# MCU.net
KiCad netlist of a schematic drawn in Altium Designer
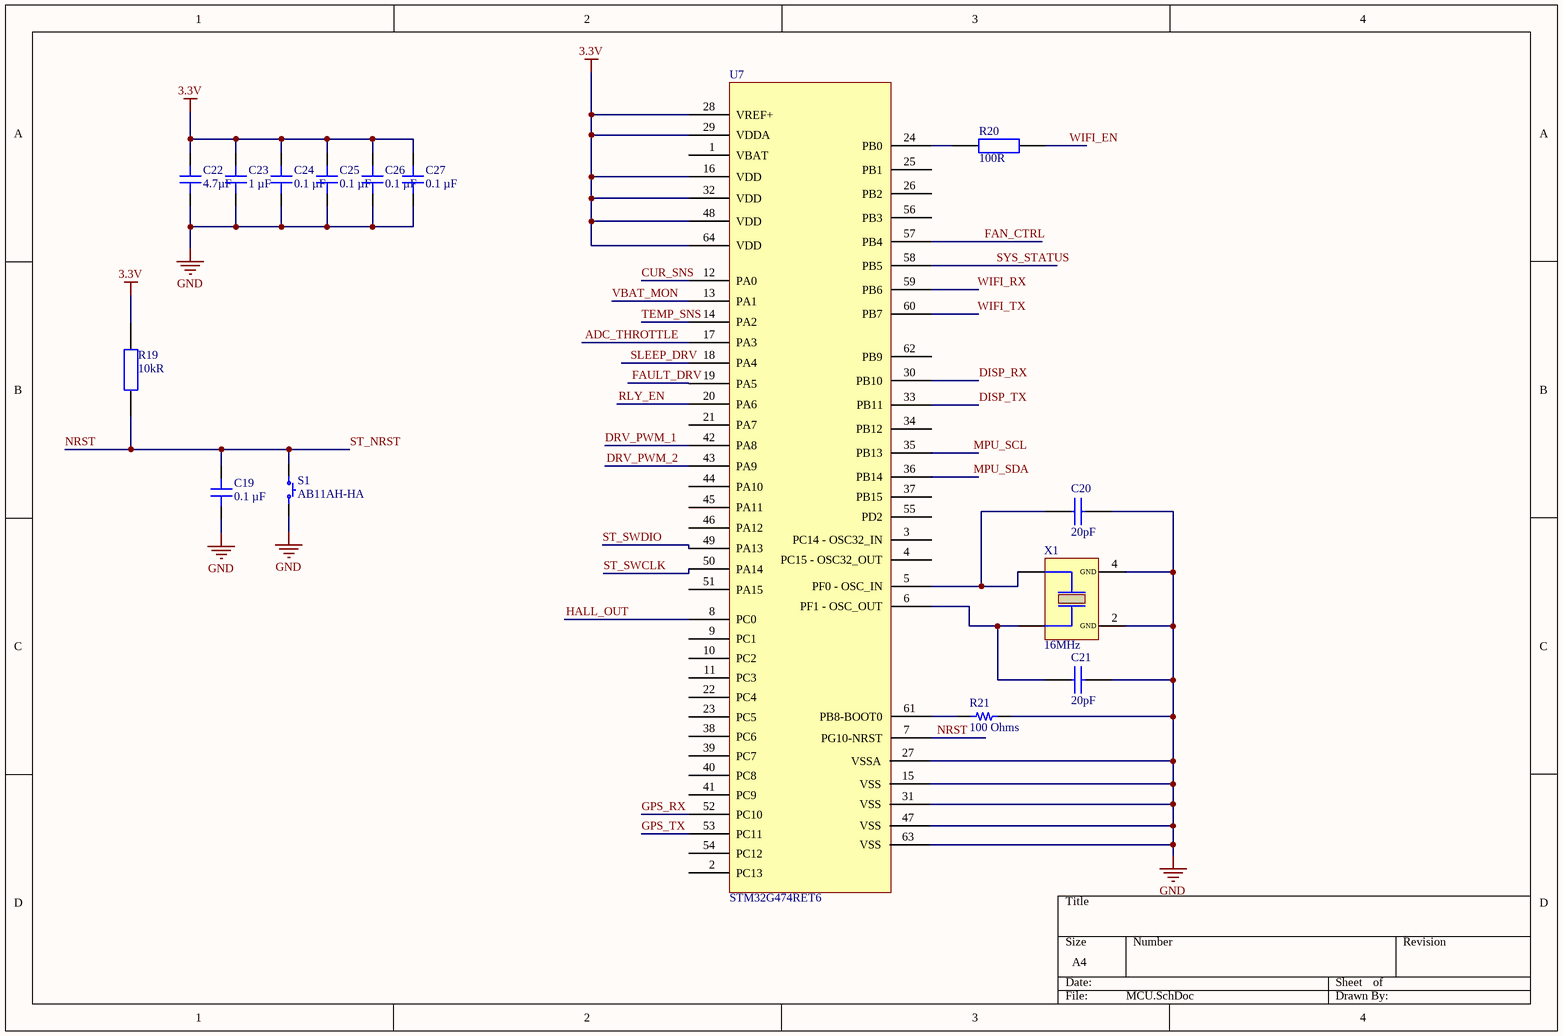
[diagram p0: MCU.SchDoc]

(export (version "E")
  (design (tool "Eeschema 10.0.6"))
  (components
    (comp (ref "C19")
      (value "0.1 µF")
      (footprint "CAP 0603_1608")
      (description "CAP CER 0.1UF 16V X7R 0603")
      (fields
        (field (name "PART NUMBER") "CS0603KRX7R7BB104")
        (field (name "CAPACITANCE") "0.1 µF")
        (field (name "MANUFACTURER") "Yageo")
      )
      (libsource (lib "Celestial Altium Library - altium_library") (part "Capacitor"))
    )
    (comp (ref "C20")
      (value "CL10C200JB8NNNC")
      (footprint "CAP_0603")
      (description "CAP CER 20pF %5 0603 SMD")
      (fields
        (field (name "MANUFACTURER") "Samsung")
        (field (name "TOLERANCE") "5%")
        (field (name "CAPACITANCE") "20pF")
        (field (name "DESIGNED BY") "BERK")
      )
      (libsource (lib "UDEMY_Library") (part "CAP CER 20pF 0603"))
    )
    (comp (ref "C21")
      (value "CL10C200JB8NNNC")
      (footprint "CAP_0603")
      (description "CAP CER 20pF %5 0603 SMD")
      (fields
        (field (name "MANUFACTURER") "Samsung")
        (field (name "TOLERANCE") "5%")
        (field (name "CAPACITANCE") "20pF")
        (field (name "DESIGNED BY") "BERK")
      )
      (libsource (lib "UDEMY_Library") (part "CAP CER 20pF 0603"))
    )
    (comp (ref "C22")
      (value "4.7µF")
      (footprint "CAP 0805_2012")
      (description "CAP CER 4.7UF 16V X5R 0805")
      (fields
        (field (name "PART NUMBER") "0805YD475MAT2A")
        (field (name "CAPACITANCE") "4.7µF")
        (field (name "MANUFACTURER") "AVX Corporation")
      )
      (libsource (lib "Celestial Altium Library - altium_library") (part "Capacitor"))
    )
    (comp (ref "C23")
      (value "1 µF")
      (footprint "CAP 0805_2012")
      (description "CAP CER 1UF 16V X7R 0805")
      (fields
        (field (name "PART NUMBER") "EMK212B7105KGHTR")
        (field (name "CAPACITANCE") "1 µF")
        (field (name "MANUFACTURER") "Taiyo Yuden")
      )
      (libsource (lib "Celestial Altium Library - altium_library") (part "Capacitor"))
    )
    (comp (ref "C24")
      (value "0.1 µF")
      (footprint "CAP 0603_1608")
      (description "CAP CER 0.1UF 16V X7R 0603")
      (fields
        (field (name "PART NUMBER") "CS0603KRX7R7BB104")
        (field (name "CAPACITANCE") "0.1 µF")
        (field (name "MANUFACTURER") "Yageo")
      )
      (libsource (lib "Celestial Altium Library - altium_library") (part "Capacitor"))
    )
    (comp (ref "C25")
      (value "0.1 µF")
      (footprint "CAP 0603_1608")
      (description "CAP CER 0.1UF 16V X7R 0603")
      (fields
        (field (name "PART NUMBER") "CS0603KRX7R7BB104")
        (field (name "CAPACITANCE") "0.1 µF")
        (field (name "MANUFACTURER") "Yageo")
      )
      (libsource (lib "Celestial Altium Library - altium_library") (part "Capacitor"))
    )
    (comp (ref "C26")
      (value "0.1 µF")
      (footprint "CAP 0603_1608")
      (description "CAP CER 0.1UF 16V X7R 0603")
      (fields
        (field (name "PART NUMBER") "CS0603KRX7R7BB104")
        (field (name "CAPACITANCE") "0.1 µF")
        (field (name "MANUFACTURER") "Yageo")
      )
      (libsource (lib "Celestial Altium Library - altium_library") (part "Capacitor"))
    )
    (comp (ref "C27")
      (value "0.1 µF")
      (footprint "CAP 0603_1608")
      (description "CAP CER 0.1UF 16V X7R 0603")
      (fields
        (field (name "PART NUMBER") "CS0603KRX7R7BB104")
        (field (name "CAPACITANCE") "0.1 µF")
        (field (name "MANUFACTURER") "Yageo")
      )
      (libsource (lib "Celestial Altium Library - altium_library") (part "Capacitor"))
    )
    (comp (ref "R19")
      (value "RC0603FR-0710KL")
      (footprint "RES_0603")
      (description "RES 10K %1 OHM 0603 SMD")
      (fields
        (field (name "MANUFACTURER") "Yageo")
        (field (name "TOLERANCE") "1%")
        (field (name "RESISTANCE") "10kR")
        (field (name "DESIGNED BY") "BERK")
      )
      (libsource (lib "UDEMY_Library") (part "RES 10K OHM 0603"))
    )
    (comp (ref "R20")
      (value "RC0603JR-07100RL")
      (footprint "RES_0603")
      (description "RES 100 %5 OHM 0603 SMD")
      (fields
        (field (name "MANUFACTURER") "Yageo")
        (field (name "TOLERANCE") "5%")
        (field (name "RESISTANCE") "100R")
        (field (name "DESIGNED BY") "BERK")
      )
      (libsource (lib "UDEMY_Library") (part "RES 100 OHM 0603"))
    )
    (comp (ref "R21")
      (value "100 Ohms")
      (footprint "RES 0603_1608")
      (description "RES SMD 100 OHM 5% 1/4W 0603")
      (fields (field (name "PART NUMBER") "ESR03EZPJ101") (field (name "MANUFACTURER") "Rohm Semiconductor"))
      (libsource (lib "Celestial Altium Library - altium_library") (part "Resistor"))
    )
    (comp (ref "S1")
      (value "AB11AH-HA")
      (footprint "NKK AB11AH-HA")
      (description "SWITCH PUSH SPST-NO 0.4VA 28V")
      (fields (field (name "MANUFACTURER") "NKK Switches"))
      (libsource (lib "Celestial Altium Library - altium_library") (part "NKK AB11AH-HA"))
    )
    (comp (ref "U7")
      (value "STM32G474RET6")
      (footprint "STM32G474RET6")
      (description "MCU 32-bit ARM Cortex M4 RISC 512KB Flash 1.8V/2.5V/3.3V 64-Pin LQFP Tray")
      (fields (field (name "MANUFACTURER") "STMicroelectronics"))
      (libsource (lib "TIDA_00620") (part "STM32G474RET6"))
    )
    (comp (ref "X1")
      (value "ECS-160-20-30B-TR")
      (footprint "ECS")
      (description "CRYSTAL 16.0000MHZ 20PF SMD")
      (fields
        (field (name "MANUFACTURER") "ECS International")
        (field (name "TOLERANCE") "50ppm")
        (field (name "FREQUENCY") "16MHz")
        (field (name "DESIGNED BY") "BERK")
      )
      (libsource (lib "UDEMY_Library") (part "CRYSTAL 16MHz"))
    )
  )
  (nets
    (net (code "1") (name "/ADC_THROTTLE") (class "Default")
      (node (ref "U7") (pin "17") (pinfunction "PA3_17") (pintype "passive"))
    )
    (net (code "2") (name "/CUR_SNS") (class "Default")
      (node (ref "U7") (pin "12") (pinfunction "PA0_12") (pintype "passive"))
    )
    (net (code "3") (name "/DISP_RX") (class "Default")
      (node (ref "U7") (pin "30") (pinfunction "PB10_30") (pintype "passive"))
    )
    (net (code "4") (name "/DISP_TX") (class "Default")
      (node (ref "U7") (pin "33") (pinfunction "PB11_33") (pintype "passive"))
    )
    (net (code "5") (name "/DRV_PWM_1") (class "Default")
      (node (ref "U7") (pin "42") (pinfunction "PA8_42") (pintype "passive"))
    )
    (net (code "6") (name "/DRV_PWM_2") (class "Default")
      (node (ref "U7") (pin "43") (pinfunction "PA9_43") (pintype "passive"))
    )
    (net (code "7") (name "/FAN_CTRL") (class "Default")
      (node (ref "U7") (pin "57") (pinfunction "PB4_57") (pintype "passive"))
    )
    (net (code "8") (name "/FAULT_DRV") (class "Default")
      (node (ref "U7") (pin "19") (pinfunction "PA5_19") (pintype "passive"))
    )
    (net (code "9") (name "/GPS_RX") (class "Default")
      (node (ref "U7") (pin "52") (pinfunction "PC10_52") (pintype "passive"))
    )
    (net (code "10") (name "/GPS_TX") (class "Default")
      (node (ref "U7") (pin "53") (pinfunction "PC11_53") (pintype "passive"))
    )
    (net (code "11") (name "/HALL_OUT") (class "Default")
      (node (ref "U7") (pin "8") (pinfunction "PC0_8") (pintype "passive"))
    )
    (net (code "12") (name "/MPU_SCL") (class "Default")
      (node (ref "U7") (pin "35") (pinfunction "PB13_35") (pintype "passive"))
    )
    (net (code "13") (name "/MPU_SDA") (class "Default")
      (node (ref "U7") (pin "36") (pinfunction "PB14_36") (pintype "passive"))
    )
    (net (code "14") (name "/NRST") (class "Default")
      (node (ref "C19") (pin "2") (pinfunction "2_2") (pintype "passive"))
      (node (ref "R19") (pin "1") (pinfunction "1_1") (pintype "passive"))
      (node (ref "S1") (pin "1") (pinfunction "1_1") (pintype "passive"))
      (node (ref "U7") (pin "7") (pinfunction "PG10-NRST_7") (pintype "passive"))
    )
    (net (code "15") (name "/RLY_EN") (class "Default")
      (node (ref "U7") (pin "20") (pinfunction "PA6_20") (pintype "passive"))
    )
    (net (code "16") (name "/SLEEP_DRV") (class "Default")
      (node (ref "U7") (pin "18") (pinfunction "PA4_18") (pintype "passive"))
    )
    (net (code "17") (name "/ST_SWCLK") (class "Default")
      (node (ref "U7") (pin "50") (pinfunction "PA14_50") (pintype "passive"))
    )
    (net (code "18") (name "/ST_SWDIO") (class "Default")
      (node (ref "U7") (pin "49") (pinfunction "PA13_49") (pintype "passive"))
    )
    (net (code "19") (name "/SYS_STATUS") (class "Default")
      (node (ref "U7") (pin "58") (pinfunction "PB5_58") (pintype "passive"))
    )
    (net (code "20") (name "/TEMP_SNS") (class "Default")
      (node (ref "U7") (pin "14") (pinfunction "PA2_14") (pintype "passive"))
    )
    (net (code "21") (name "/VBAT_MON") (class "Default")
      (node (ref "U7") (pin "13") (pinfunction "PA1_13") (pintype "passive"))
    )
    (net (code "22") (name "/WIFI_EN") (class "Default")
      (node (ref "R20") (pin "2") (pinfunction "2_2") (pintype "passive"))
    )
    (net (code "23") (name "/WIFI_RX") (class "Default")
      (node (ref "U7") (pin "59") (pinfunction "PB6_59") (pintype "passive"))
    )
    (net (code "24") (name "/WIFI_TX") (class "Default")
      (node (ref "U7") (pin "60") (pinfunction "PB7_60") (pintype "passive"))
    )
    (net (code "25") (name "3.3V") (class "Default")
      (node (ref "C22") (pin "2") (pinfunction "2_2") (pintype "passive"))
      (node (ref "C23") (pin "2") (pinfunction "2_2") (pintype "passive"))
      (node (ref "C24") (pin "2") (pinfunction "2_2") (pintype "passive"))
      (node (ref "C25") (pin "2") (pinfunction "2_2") (pintype "passive"))
      (node (ref "C26") (pin "2") (pinfunction "2_2") (pintype "passive"))
      (node (ref "C27") (pin "2") (pinfunction "2_2") (pintype "passive"))
      (node (ref "R19") (pin "2") (pinfunction "2_2") (pintype "passive"))
      (node (ref "U7") (pin "16") (pinfunction "VDD_16") (pintype "passive"))
      (node (ref "U7") (pin "28") (pinfunction "VREF+_28") (pintype "passive"))
      (node (ref "U7") (pin "29") (pinfunction "VDDA_29") (pintype "passive"))
      (node (ref "U7") (pin "32") (pinfunction "VDD_32") (pintype "passive"))
      (node (ref "U7") (pin "48") (pinfunction "VDD_48") (pintype "passive"))
      (node (ref "U7") (pin "64") (pinfunction "VDD_64") (pintype "passive"))
    )
    (net (code "26") (name "GND") (class "Default")
      (node (ref "C19") (pin "1") (pinfunction "1_1") (pintype "passive"))
      (node (ref "C20") (pin "2") (pinfunction "2_2") (pintype "passive"))
      (node (ref "C21") (pin "2") (pinfunction "2_2") (pintype "passive"))
      (node (ref "C22") (pin "1") (pinfunction "1_1") (pintype "passive"))
      (node (ref "C23") (pin "1") (pinfunction "1_1") (pintype "passive"))
      (node (ref "C24") (pin "1") (pinfunction "1_1") (pintype "passive"))
      (node (ref "C25") (pin "1") (pinfunction "1_1") (pintype "passive"))
      (node (ref "C26") (pin "1") (pinfunction "1_1") (pintype "passive"))
      (node (ref "C27") (pin "1") (pinfunction "1_1") (pintype "passive"))
      (node (ref "R21") (pin "2") (pinfunction "2_2") (pintype "passive"))
      (node (ref "S1") (pin "3") (pinfunction "3_3") (pintype "passive"))
      (node (ref "U7") (pin "15") (pinfunction "VSS_15") (pintype "passive"))
      (node (ref "U7") (pin "27") (pinfunction "VSSA_27") (pintype "passive"))
      (node (ref "U7") (pin "31") (pinfunction "VSS_31") (pintype "passive"))
      (node (ref "U7") (pin "47") (pinfunction "VSS_47") (pintype "passive"))
      (node (ref "U7") (pin "63") (pinfunction "VSS_63") (pintype "passive"))
      (node (ref "X1") (pin "2") (pinfunction "GND_2") (pintype "passive"))
      (node (ref "X1") (pin "4") (pinfunction "GND_4") (pintype "passive"))
    )
    (net (code "27") (name "Net-(U7-PB0)") (class "Default")
      (node (ref "R20") (pin "1") (pinfunction "1_1") (pintype "passive"))
      (node (ref "U7") (pin "24") (pinfunction "PB0_24") (pintype "passive"))
    )
    (net (code "28") (name "Net-(U7-PB8-BOOT0)") (class "Default")
      (node (ref "R21") (pin "1") (pinfunction "1_1") (pintype "passive"))
      (node (ref "U7") (pin "61") (pinfunction "PB8-BOOT0_61") (pintype "passive"))
    )
    (net (code "29") (name "Net-(U7-PF0_-_OSC_IN)") (class "Default")
      (node (ref "C20") (pin "1") (pinfunction "1_1") (pintype "passive"))
      (node (ref "U7") (pin "5") (pinfunction "PF0_-_OSC_IN_5") (pintype "passive"))
      (node (ref "X1") (pin "3") (pinfunction "3_3") (pintype "passive"))
    )
    (net (code "30") (name "Net-(U7-PF1_-_OSC_OUT)") (class "Default")
      (node (ref "C21") (pin "1") (pinfunction "1_1") (pintype "passive"))
      (node (ref "U7") (pin "6") (pinfunction "PF1_-_OSC_OUT_6") (pintype "passive"))
      (node (ref "X1") (pin "1") (pinfunction "1_1") (pintype "passive"))
    )
    (net (code "31") (name "unconnected-(U7-PA7-Pad21)") (class "Default")
      (node (ref "U7") (pin "21") (pinfunction "PA7_21") (pintype "passive"))
    )
    (net (code "32") (name "unconnected-(U7-PA10-Pad44)") (class "Default")
      (node (ref "U7") (pin "44") (pinfunction "PA10_44") (pintype "passive"))
    )
    (net (code "33") (name "unconnected-(U7-PA11-Pad45)") (class "Default")
      (node (ref "U7") (pin "45") (pinfunction "PA11_45") (pintype "passive"))
    )
    (net (code "34") (name "unconnected-(U7-PA12-Pad46)") (class "Default")
      (node (ref "U7") (pin "46") (pinfunction "PA12_46") (pintype "passive"))
    )
    (net (code "35") (name "unconnected-(U7-PA15-Pad51)") (class "Default")
      (node (ref "U7") (pin "51") (pinfunction "PA15_51") (pintype "passive"))
    )
    (net (code "36") (name "unconnected-(U7-PB1-Pad25)") (class "Default")
      (node (ref "U7") (pin "25") (pinfunction "PB1_25") (pintype "passive"))
    )
    (net (code "37") (name "unconnected-(U7-PB2-Pad26)") (class "Default")
      (node (ref "U7") (pin "26") (pinfunction "PB2_26") (pintype "passive"))
    )
    (net (code "38") (name "unconnected-(U7-PB3-Pad56)") (class "Default")
      (node (ref "U7") (pin "56") (pinfunction "PB3_56") (pintype "passive"))
    )
    (net (code "39") (name "unconnected-(U7-PB9-Pad62)") (class "Default")
      (node (ref "U7") (pin "62") (pinfunction "PB9_62") (pintype "passive"))
    )
    (net (code "40") (name "unconnected-(U7-PB12-Pad34)") (class "Default")
      (node (ref "U7") (pin "34") (pinfunction "PB12_34") (pintype "passive"))
    )
    (net (code "41") (name "unconnected-(U7-PB15-Pad37)") (class "Default")
      (node (ref "U7") (pin "37") (pinfunction "PB15_37") (pintype "passive"))
    )
    (net (code "42") (name "unconnected-(U7-PC1-Pad9)") (class "Default")
      (node (ref "U7") (pin "9") (pinfunction "PC1_9") (pintype "passive"))
    )
    (net (code "43") (name "unconnected-(U7-PC2-Pad10)") (class "Default")
      (node (ref "U7") (pin "10") (pinfunction "PC2_10") (pintype "passive"))
    )
    (net (code "44") (name "unconnected-(U7-PC3-Pad11)") (class "Default")
      (node (ref "U7") (pin "11") (pinfunction "PC3_11") (pintype "passive"))
    )
    (net (code "45") (name "unconnected-(U7-PC4-Pad22)") (class "Default")
      (node (ref "U7") (pin "22") (pinfunction "PC4_22") (pintype "passive"))
    )
    (net (code "46") (name "unconnected-(U7-PC5-Pad23)") (class "Default")
      (node (ref "U7") (pin "23") (pinfunction "PC5_23") (pintype "passive"))
    )
    (net (code "47") (name "unconnected-(U7-PC6-Pad38)") (class "Default")
      (node (ref "U7") (pin "38") (pinfunction "PC6_38") (pintype "passive"))
    )
    (net (code "48") (name "unconnected-(U7-PC7-Pad39)") (class "Default")
      (node (ref "U7") (pin "39") (pinfunction "PC7_39") (pintype "passive"))
    )
    (net (code "49") (name "unconnected-(U7-PC8-Pad40)") (class "Default")
      (node (ref "U7") (pin "40") (pinfunction "PC8_40") (pintype "passive"))
    )
    (net (code "50") (name "unconnected-(U7-PC9-Pad41)") (class "Default")
      (node (ref "U7") (pin "41") (pinfunction "PC9_41") (pintype "passive"))
    )
    (net (code "51") (name "unconnected-(U7-PC12-Pad54)") (class "Default")
      (node (ref "U7") (pin "54") (pinfunction "PC12_54") (pintype "passive"))
    )
    (net (code "52") (name "unconnected-(U7-PC13-Pad2)") (class "Default")
      (node (ref "U7") (pin "2") (pinfunction "PC13_2") (pintype "passive"))
    )
    (net (code "53") (name "unconnected-(U7-PC14_-_OSC32_IN-Pad3)") (class "Default")
      (node (ref "U7") (pin "3") (pinfunction "PC14_-_OSC32_IN_3") (pintype "passive"))
    )
    (net (code "54") (name "unconnected-(U7-PC15_-_OSC32_OUT-Pad4)") (class "Default")
      (node (ref "U7") (pin "4") (pinfunction "PC15_-_OSC32_OUT_4") (pintype "passive"))
    )
    (net (code "55") (name "unconnected-(U7-PD2-Pad55)") (class "Default")
      (node (ref "U7") (pin "55") (pinfunction "PD2_55") (pintype "passive"))
    )
    (net (code "56") (name "unconnected-(U7-VBAT-Pad1)") (class "Default")
      (node (ref "U7") (pin "1") (pinfunction "VBAT_1") (pintype "passive"))
    )
  )
)
